# OpenSwitch_Power.net
KiCad netlist of a schematic drawn in Altium Designer
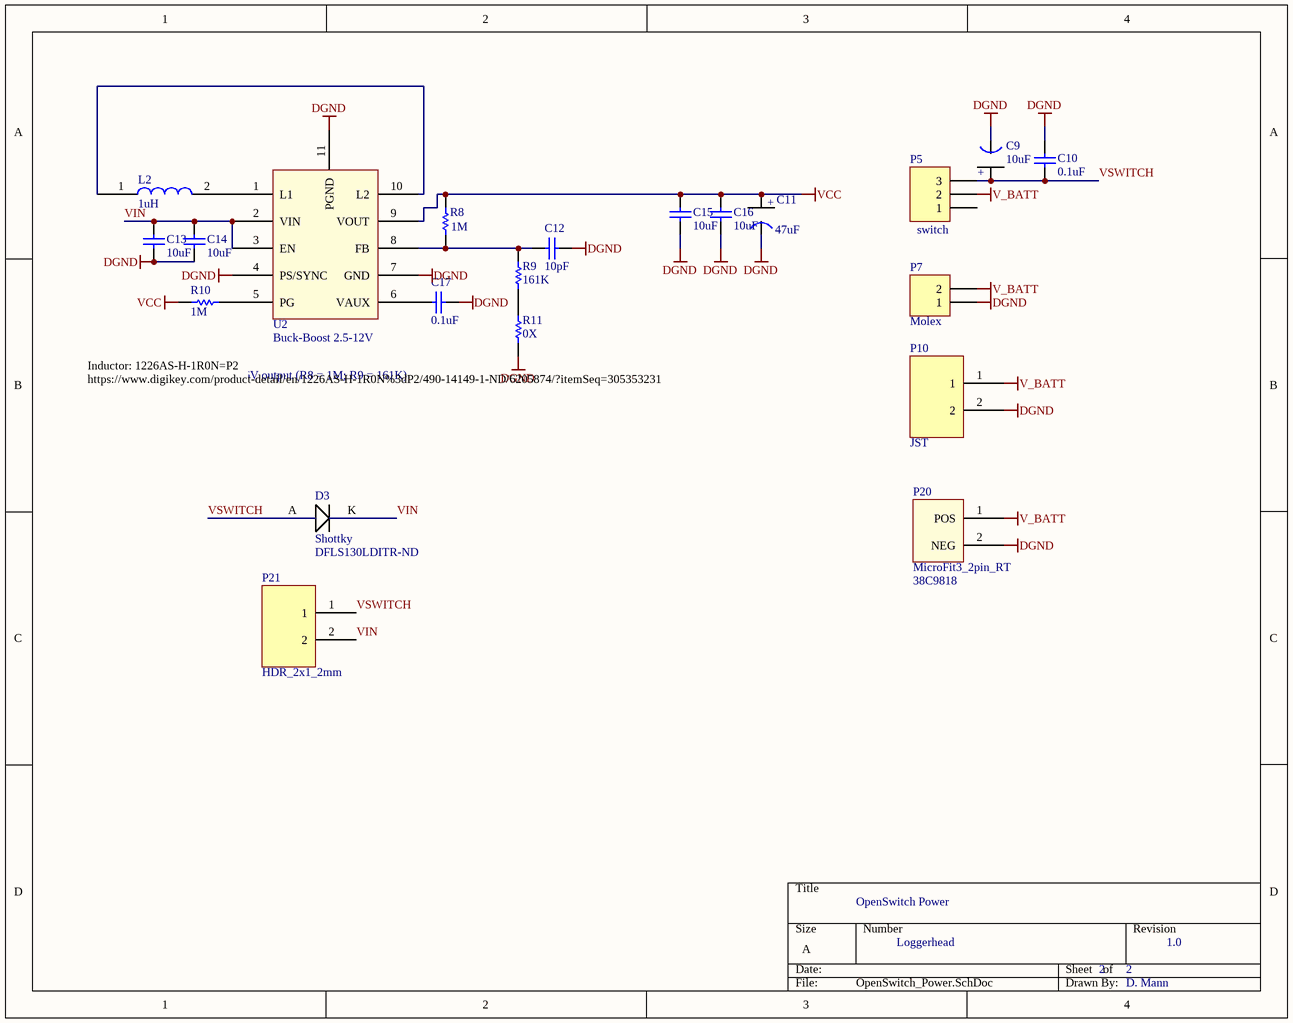
[diagram p0: OpenSwitch_Power.SchDoc]

(export (version "E")
  (design (tool "Eeschema 10.0.6"))
  (components
    (comp (ref "C9") (value "10uF") (footprint "Tant0805") (libsource (lib "Loggerhead") (part "Tant0805")))
    (comp (ref "C10")
      (value "0.1uF")
      (footprint "0402")
      (description "Ceramic Chip Capacitor - Standard")
      (fields (field (name "PUBLISHER") "Altium Limited"))
      (libsource (lib "KEMET Chip Capacitor") (part "C0402"))
    )
    (comp (ref "C11") (value "47uF") (footprint "Tant0805") (libsource (lib "Loggerhead") (part "Tant0805")))
    (comp (ref "C12")
      (value "10pF")
      (footprint "0402")
      (description "Ceramic Chip Capacitor - Standard")
      (fields (field (name "PUBLISHER") "Altium Limited"))
      (libsource (lib "KEMET Chip Capacitor") (part "C0402"))
    )
    (comp (ref "C13")
      (value "10uF")
      (footprint "0603")
      (description "Ceramic Chip Capacitor - Standard")
      (fields (field (name "PUBLISHER") "Altium Limited"))
      (libsource (lib "KEMET Chip Capacitor") (part "C0603"))
    )
    (comp (ref "C14")
      (value "10uF")
      (footprint "0603")
      (description "Ceramic Chip Capacitor - Standard")
      (fields (field (name "PUBLISHER") "Altium Limited"))
      (libsource (lib "KEMET Chip Capacitor") (part "C0603"))
    )
    (comp (ref "C15")
      (value "10uF")
      (footprint "0603")
      (description "Ceramic Chip Capacitor - Standard")
      (fields (field (name "PUBLISHER") "Altium Limited"))
      (libsource (lib "KEMET Chip Capacitor") (part "C0603"))
    )
    (comp (ref "C16")
      (value "10uF")
      (footprint "0603")
      (description "Ceramic Chip Capacitor - Standard")
      (fields (field (name "PUBLISHER") "Altium Limited"))
      (libsource (lib "KEMET Chip Capacitor") (part "C0603"))
    )
    (comp (ref "C17")
      (value "0.1uF")
      (footprint "0402")
      (description "Ceramic Chip Capacitor - Standard")
      (fields (field (name "PUBLISHER") "Altium Limited"))
      (libsource (lib "KEMET Chip Capacitor") (part "C0402"))
    )
    (comp (ref "D3")
      (value "Shottky")
      (footprint "DFLS130")
      (fields (field (name "SUPPLIER PART NUMBER 1") "DFLS130LDITR-ND"))
      (libsource (lib "Loggerhead") (part "DFLS130"))
    )
    (comp (ref "L2")
      (value "1uH")
      (footprint "Inductor_NLV32T")
      (libsource (lib "Loggerhead") (part "Inductor_NLV32T"))
    )
    (comp (ref "P5")
      (value "switch")
      (footprint "HDR1X3")
      (description "Header, 3-Pin")
      (fields (field (name "PUBLISHER") "Altium Limited"))
      (libsource (lib "Miscellaneous Connectors") (part "Header 3"))
    )
    (comp (ref "P7")
      (value "Molex")
      (footprint "HDR1X2")
      (description "Header, 2-Pin")
      (fields (field (name "PUBLISHER") "Altium Limited"))
      (libsource (lib "Miscellaneous Connectors") (part "Header 2"))
    )
    (comp (ref "P10")
      (value "JST")
      (footprint "HDR_2x1_2mm")
      (libsource (lib "Loggerhead") (part "HDR_2x1_2mm"))
    )
    (comp (ref "P20")
      (value "MicroFit3_2pin_RT")
      (footprint "Microfit 3 - 2 pin RT")
      (fields (field (name "SUPPLIER PART NUMBER 1") "38C9818"))
      (libsource (lib "Loggerhead") (part "MicroFit3_2pin_RT"))
    )
    (comp (ref "P21")
      (value "HDR_2x1_2mm")
      (footprint "HDR_2x1_2mm")
      (libsource (lib "Loggerhead") (part "HDR_2x1_2mm"))
    )
    (comp (ref "R8")
      (value "1M")
      (footprint "3-0603")
      (fields (field (name "PUBLISHER") "Altium Limited"))
      (libsource (lib "Panasonic Resistor") (part "ERJ3RK"))
    )
    (comp (ref "R9")
      (value "161K")
      (footprint "3-0603")
      (fields (field (name "PUBLISHER") "Altium Limited"))
      (libsource (lib "Panasonic Resistor") (part "ERJ3RK"))
    )
    (comp (ref "R10")
      (value "1M")
      (footprint "3-0603")
      (fields (field (name "PUBLISHER") "Altium Limited"))
      (libsource (lib "Panasonic Resistor") (part "ERJ3RK"))
    )
    (comp (ref "R11")
      (value "0X")
      (footprint "3-0603")
      (fields (field (name "PUBLISHER") "Altium Limited"))
      (libsource (lib "Panasonic Resistor") (part "ERJ3RK"))
    )
    (comp (ref "U2")
      (value "Buck-Boost 2.5-12V")
      (footprint "TPS63060")
      (description "TPS63060")
      (libsource (lib "Loggerhead") (part "TPS63060"))
    )
  )
  (nets
    (net (code "1") (name "/VIN") (class "Default")
      (node (ref "C13") (pin "2") (pinfunction "2_2") (pintype "passive"))
      (node (ref "C14") (pin "2") (pinfunction "2_2") (pintype "passive"))
      (node (ref "D3") (pin "K") (pintype "passive"))
      (node (ref "P21") (pin "2") (pinfunction "2_2") (pintype "passive"))
      (node (ref "U2") (pin "2") (pinfunction "VIN_2") (pintype "passive"))
      (node (ref "U2") (pin "3") (pinfunction "EN_3") (pintype "passive"))
    )
    (net (code "2") (name "/VSWITCH") (class "Default")
      (node (ref "C10") (pin "1") (pinfunction "1_1") (pintype "passive"))
      (node (ref "C9") (pin "2") (pinfunction "+_2") (pintype "passive"))
      (node (ref "D3") (pin "A") (pintype "passive"))
      (node (ref "P21") (pin "1") (pinfunction "1_1") (pintype "passive"))
      (node (ref "P5") (pin "3") (pinfunction "3_3") (pintype "passive"))
    )
    (net (code "3") (name "DGND") (class "Default")
      (node (ref "C10") (pin "2") (pinfunction "2_2") (pintype "passive"))
      (node (ref "C11") (pin "1") (pinfunction "GND_1") (pintype "passive"))
      (node (ref "C12") (pin "2") (pinfunction "2_2") (pintype "passive"))
      (node (ref "C13") (pin "1") (pinfunction "1_1") (pintype "passive"))
      (node (ref "C14") (pin "1") (pinfunction "1_1") (pintype "passive"))
      (node (ref "C15") (pin "1") (pinfunction "1_1") (pintype "passive"))
      (node (ref "C16") (pin "1") (pinfunction "1_1") (pintype "passive"))
      (node (ref "C17") (pin "2") (pinfunction "2_2") (pintype "passive"))
      (node (ref "C9") (pin "1") (pinfunction "GND_1") (pintype "passive"))
      (node (ref "P10") (pin "2") (pinfunction "2_2") (pintype "passive"))
      (node (ref "P20") (pin "2") (pinfunction "NEG_2") (pintype "passive"))
      (node (ref "P7") (pin "1") (pinfunction "1_1") (pintype "passive"))
      (node (ref "R11") (pin "1") (pinfunction "1_1") (pintype "passive"))
      (node (ref "U2") (pin "11") (pinfunction "PGND_11") (pintype "passive"))
      (node (ref "U2") (pin "4") (pinfunction "PS/SYNC_4") (pintype "passive"))
      (node (ref "U2") (pin "7") (pinfunction "GND_7") (pintype "passive"))
    )
    (net (code "4") (name "Net-(R11-Pad2)") (class "Default")
      (node (ref "R11") (pin "2") (pinfunction "2_2") (pintype "passive"))
      (node (ref "R9") (pin "1") (pinfunction "1_1") (pintype "passive"))
    )
    (net (code "5") (name "Net-(U2-FB)") (class "Default")
      (node (ref "C12") (pin "1") (pinfunction "1_1") (pintype "passive"))
      (node (ref "R8") (pin "1") (pinfunction "1_1") (pintype "passive"))
      (node (ref "R9") (pin "2") (pinfunction "2_2") (pintype "passive"))
      (node (ref "U2") (pin "8") (pinfunction "FB_8") (pintype "passive"))
    )
    (net (code "6") (name "Net-(U2-L1)") (class "Default")
      (node (ref "L2") (pin "2") (pinfunction "2_2") (pintype "passive"))
      (node (ref "U2") (pin "1") (pinfunction "L1_1") (pintype "passive"))
    )
    (net (code "7") (name "Net-(U2-L2)") (class "Default")
      (node (ref "L2") (pin "1") (pinfunction "1_1") (pintype "passive"))
      (node (ref "U2") (pin "10") (pinfunction "L2_10") (pintype "passive"))
    )
    (net (code "8") (name "Net-(U2-PG)") (class "Default")
      (node (ref "R10") (pin "2") (pinfunction "2_2") (pintype "passive"))
      (node (ref "U2") (pin "5") (pinfunction "PG_5") (pintype "passive"))
    )
    (net (code "9") (name "Net-(U2-VAUX)") (class "Default")
      (node (ref "C17") (pin "1") (pinfunction "1_1") (pintype "passive"))
      (node (ref "U2") (pin "6") (pinfunction "VAUX_6") (pintype "passive"))
    )
    (net (code "10") (name "VCC") (class "Default")
      (node (ref "C11") (pin "2") (pinfunction "+_2") (pintype "passive"))
      (node (ref "C15") (pin "2") (pinfunction "2_2") (pintype "passive"))
      (node (ref "C16") (pin "2") (pinfunction "2_2") (pintype "passive"))
      (node (ref "R10") (pin "1") (pinfunction "1_1") (pintype "passive"))
      (node (ref "R8") (pin "2") (pinfunction "2_2") (pintype "passive"))
      (node (ref "U2") (pin "9") (pinfunction "VOUT_9") (pintype "passive"))
    )
    (net (code "11") (name "V_BATT") (class "Default")
      (node (ref "P10") (pin "1") (pinfunction "1_1") (pintype "passive"))
      (node (ref "P20") (pin "1") (pinfunction "POS_1") (pintype "passive"))
      (node (ref "P5") (pin "2") (pinfunction "2_2") (pintype "passive"))
      (node (ref "P7") (pin "2") (pinfunction "2_2") (pintype "passive"))
    )
    (net (code "12") (name "unconnected-(P5-Pad1)") (class "Default")
      (node (ref "P5") (pin "1") (pinfunction "1_1") (pintype "passive"))
    )
  )
)
